# ACC_Register_Electronic_Scheme_2021-10-0.net
KiCad netlist of a schematic drawn in Altium Designer
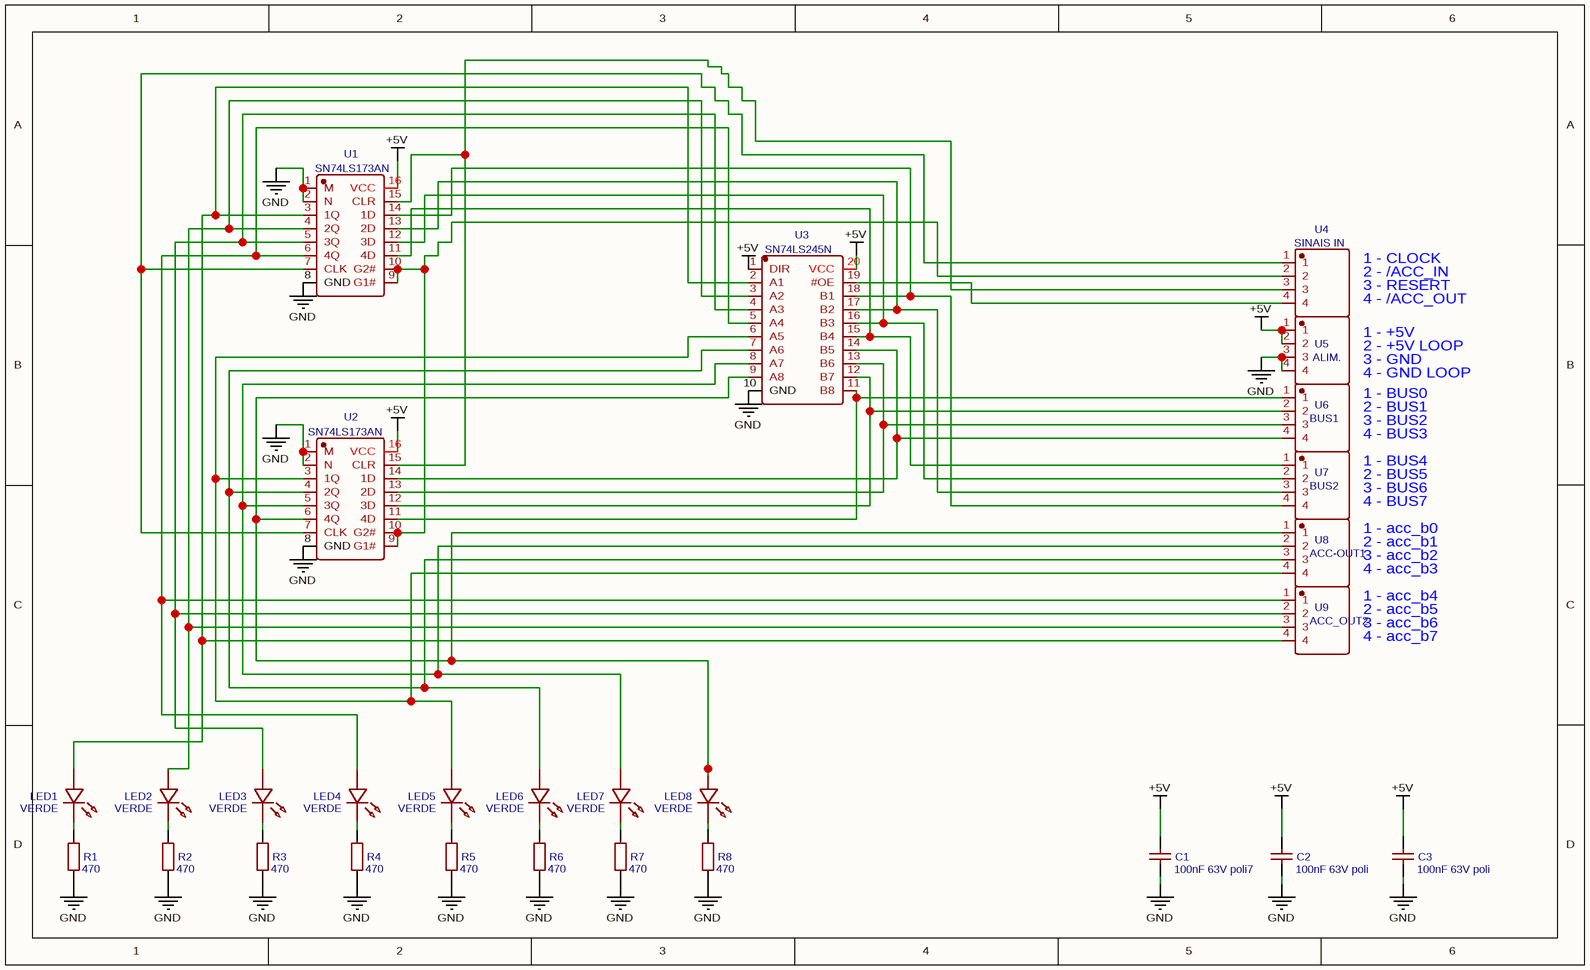
[diagram p0: ACC Register Electronic Scheme_2021-10-02.schdoc]

(export (version "E")
  (design (tool "Eeschema 10.0.6"))
  (components
    (comp (ref "C1")
      (value "100nF 63V poli7")
      (fields
        (field (name "BOM_SUPPLIER PART") "C444741")
        (field (name "BOM_MANUFACTURER PART") "SR305C105KAR")
        (field (name "CONTRIBUTOR") "LCSC")
      )
      (libsource (lib "altium-import") (part "root_3_100nF 63V poli7_"))
    )
    (comp (ref "C2")
      (value "100nF 63V poli")
      (fields
        (field (name "BOM_SUPPLIER PART") "C444741")
        (field (name "BOM_MANUFACTURER PART") "SR305C105KAR")
        (field (name "CONTRIBUTOR") "LCSC")
      )
      (libsource (lib "altium-import") (part "root_3_100nF 63V poli_"))
    )
    (comp (ref "C3")
      (value "100nF 63V poli")
      (fields
        (field (name "BOM_SUPPLIER PART") "C444741")
        (field (name "BOM_MANUFACTURER PART") "SR305C105KAR")
        (field (name "CONTRIBUTOR") "LCSC")
      )
      (libsource (lib "altium-import") (part "root_3_100nF 63V poli_"))
    )
    (comp (ref "LED1")
      (value "VERDE")
      (fields
        (field (name "BOM_SUPPLIER PART") "C605465")
        (field (name "BOM_MANUFACTURER PART") "264-7GD")
        (field (name "CONTRIBUTOR") "LCSC")
      )
      (libsource (lib "altium-import") (part "root_1_VERDE_"))
    )
    (comp (ref "LED2")
      (value "VERDE")
      (fields
        (field (name "BOM_SUPPLIER PART") "C605465")
        (field (name "BOM_MANUFACTURER PART") "264-7GD")
        (field (name "CONTRIBUTOR") "LCSC")
      )
      (libsource (lib "altium-import") (part "root_1_VERDE_"))
    )
    (comp (ref "LED3")
      (value "VERDE")
      (fields
        (field (name "BOM_SUPPLIER PART") "C605465")
        (field (name "BOM_MANUFACTURER PART") "264-7GD")
        (field (name "CONTRIBUTOR") "LCSC")
      )
      (libsource (lib "altium-import") (part "root_1_VERDE_"))
    )
    (comp (ref "LED4")
      (value "VERDE")
      (fields
        (field (name "BOM_SUPPLIER PART") "C605465")
        (field (name "BOM_MANUFACTURER PART") "264-7GD")
        (field (name "CONTRIBUTOR") "LCSC")
      )
      (libsource (lib "altium-import") (part "root_1_VERDE_"))
    )
    (comp (ref "LED5")
      (value "VERDE")
      (fields
        (field (name "BOM_SUPPLIER PART") "C605465")
        (field (name "BOM_MANUFACTURER PART") "264-7GD")
        (field (name "CONTRIBUTOR") "LCSC")
      )
      (libsource (lib "altium-import") (part "root_1_VERDE_"))
    )
    (comp (ref "LED6")
      (value "VERDE")
      (fields
        (field (name "BOM_SUPPLIER PART") "C605465")
        (field (name "BOM_MANUFACTURER PART") "264-7GD")
        (field (name "CONTRIBUTOR") "LCSC")
      )
      (libsource (lib "altium-import") (part "root_1_VERDE_"))
    )
    (comp (ref "LED7")
      (value "VERDE")
      (fields
        (field (name "BOM_SUPPLIER PART") "C605465")
        (field (name "BOM_MANUFACTURER PART") "264-7GD")
        (field (name "CONTRIBUTOR") "LCSC")
      )
      (libsource (lib "altium-import") (part "root_1_VERDE_"))
    )
    (comp (ref "LED8")
      (value "VERDE")
      (fields
        (field (name "BOM_SUPPLIER PART") "C605465")
        (field (name "BOM_MANUFACTURER PART") "264-7GD")
        (field (name "CONTRIBUTOR") "LCSC")
      )
      (libsource (lib "altium-import") (part "root_1_VERDE_"))
    )
    (comp (ref "R1")
      (value "470")
      (fields
        (field (name "BOM_MANUFACTURER PART") "CFR02SJ0823A10")
        (field (name "BOM_SUPPLIER PART") "C69876")
      )
      (libsource (lib "altium-import") (part "root_3_470_"))
    )
    (comp (ref "R2")
      (value "470")
      (fields
        (field (name "BOM_MANUFACTURER PART") "CFR02SJ0823A10")
        (field (name "BOM_SUPPLIER PART") "C69876")
      )
      (libsource (lib "altium-import") (part "root_3_470_"))
    )
    (comp (ref "R3")
      (value "470")
      (fields
        (field (name "BOM_MANUFACTURER PART") "CFR02SJ0823A10")
        (field (name "BOM_SUPPLIER PART") "C69876")
      )
      (libsource (lib "altium-import") (part "root_3_470_"))
    )
    (comp (ref "R4")
      (value "470")
      (fields
        (field (name "BOM_MANUFACTURER PART") "CFR02SJ0823A10")
        (field (name "BOM_SUPPLIER PART") "C69876")
      )
      (libsource (lib "altium-import") (part "root_3_470_"))
    )
    (comp (ref "R5")
      (value "470")
      (fields
        (field (name "BOM_MANUFACTURER PART") "CFR02SJ0823A10")
        (field (name "BOM_SUPPLIER PART") "C69876")
      )
      (libsource (lib "altium-import") (part "root_3_470_"))
    )
    (comp (ref "R6")
      (value "470")
      (fields
        (field (name "BOM_MANUFACTURER PART") "CFR02SJ0823A10")
        (field (name "BOM_SUPPLIER PART") "C69876")
      )
      (libsource (lib "altium-import") (part "root_3_470_"))
    )
    (comp (ref "R7")
      (value "470")
      (fields
        (field (name "BOM_MANUFACTURER PART") "CFR02SJ0823A10")
        (field (name "BOM_SUPPLIER PART") "C69876")
      )
      (libsource (lib "altium-import") (part "root_3_470_"))
    )
    (comp (ref "R8")
      (value "470")
      (fields
        (field (name "BOM_MANUFACTURER PART") "CFR02SJ0823A10")
        (field (name "BOM_SUPPLIER PART") "C69876")
      )
      (libsource (lib "altium-import") (part "root_3_470_"))
    )
    (comp (ref "U1")
      (value "SN74LS173AN")
      (fields (field (name "BOM_SUPPLIER PART") "C1550125") (field (name "CONTRIBUTOR") "LCSC"))
      (libsource (lib "altium-import") (part "root_0_SN74LS173AN_"))
    )
    (comp (ref "U2")
      (value "SN74LS173AN")
      (fields (field (name "BOM_SUPPLIER PART") "C1550125") (field (name "CONTRIBUTOR") "LCSC"))
      (libsource (lib "altium-import") (part "root_0_SN74LS173AN_"))
    )
    (comp (ref "U3")
      (value "SN74LS245N")
      (fields (field (name "BOM_SUPPLIER PART") "C352966") (field (name "CONTRIBUTOR") "LCSC"))
      (libsource (lib "altium-import") (part "root_0_SN74LS245N_"))
    )
    (comp (ref "U4")
      (value "SINAIS IN")
      (fields
        (field (name "BOM_SUPPLIER PART") "C210162")
        (field (name "BOM_MANUFACTURER PART") "171825-4")
        (field (name "CONTRIBUTOR") "LCSC")
      )
      (libsource (lib "altium-import") (part "root_0_SINAIS IN_"))
    )
    (comp (ref "U5")
      (value "ALIM.")
      (fields
        (field (name "BOM_SUPPLIER PART") "C210162")
        (field (name "BOM_MANUFACTURER PART") "171825-4")
        (field (name "CONTRIBUTOR") "LCSC")
      )
      (libsource (lib "altium-import") (part "root_0_ALIM._"))
    )
    (comp (ref "U6")
      (value "BUS1")
      (fields
        (field (name "BOM_SUPPLIER PART") "C210162")
        (field (name "BOM_MANUFACTURER PART") "171825-4")
        (field (name "CONTRIBUTOR") "LCSC")
      )
      (libsource (lib "altium-import") (part "root_0_BUS1_"))
    )
    (comp (ref "U7")
      (value "BUS2")
      (fields
        (field (name "BOM_SUPPLIER PART") "C210162")
        (field (name "BOM_MANUFACTURER PART") "171825-4")
        (field (name "CONTRIBUTOR") "LCSC")
      )
      (libsource (lib "altium-import") (part "root_0_BUS2_"))
    )
    (comp (ref "U8")
      (value "ACC-OUT1")
      (fields
        (field (name "BOM_SUPPLIER PART") "C210162")
        (field (name "BOM_MANUFACTURER PART") "171825-4")
        (field (name "CONTRIBUTOR") "LCSC")
      )
      (libsource (lib "altium-import") (part "root_0_ACC-OUT1_"))
    )
    (comp (ref "U9")
      (value "ACC_OUT2")
      (fields
        (field (name "BOM_SUPPLIER PART") "C210162")
        (field (name "BOM_MANUFACTURER PART") "171825-4")
        (field (name "CONTRIBUTOR") "LCSC")
      )
      (libsource (lib "altium-import") (part "root_0_ACC_OUT2_"))
    )
  )
  (nets
    (net (code "1") (name "+5V") (class "Default")
      (node (ref "C1") (pin "1") (pinfunction "1_1") (pintype "passive"))
      (node (ref "C2") (pin "1") (pinfunction "1_1") (pintype "passive"))
      (node (ref "C3") (pin "1") (pinfunction "1_1") (pintype "passive"))
      (node (ref "U1") (pin "16") (pinfunction "VCC_16") (pintype "passive"))
      (node (ref "U2") (pin "16") (pinfunction "VCC_16") (pintype "passive"))
      (node (ref "U3") (pin "1") (pinfunction "DIR_1") (pintype "passive"))
      (node (ref "U3") (pin "20") (pinfunction "VCC_20") (pintype "passive"))
      (node (ref "U5") (pin "1") (pinfunction "1_1") (pintype "passive"))
      (node (ref "U5") (pin "2") (pinfunction "2_2") (pintype "passive"))
    )
    (net (code "2") (name "GND") (class "Default")
      (node (ref "C1") (pin "2") (pinfunction "2_2") (pintype "passive"))
      (node (ref "C2") (pin "2") (pinfunction "2_2") (pintype "passive"))
      (node (ref "C3") (pin "2") (pinfunction "2_2") (pintype "passive"))
      (node (ref "R1") (pin "2") (pinfunction "2_2") (pintype "passive"))
      (node (ref "R2") (pin "2") (pinfunction "2_2") (pintype "passive"))
      (node (ref "R3") (pin "2") (pinfunction "2_2") (pintype "passive"))
      (node (ref "R4") (pin "2") (pinfunction "2_2") (pintype "passive"))
      (node (ref "R5") (pin "2") (pinfunction "2_2") (pintype "passive"))
      (node (ref "R6") (pin "2") (pinfunction "2_2") (pintype "passive"))
      (node (ref "R7") (pin "2") (pinfunction "2_2") (pintype "passive"))
      (node (ref "R8") (pin "2") (pinfunction "2_2") (pintype "passive"))
      (node (ref "U1") (pin "1") (pinfunction "M_1") (pintype "passive"))
      (node (ref "U1") (pin "2") (pinfunction "N_2") (pintype "passive"))
      (node (ref "U1") (pin "8") (pinfunction "GND_8") (pintype "passive"))
      (node (ref "U2") (pin "1") (pinfunction "M_1") (pintype "passive"))
      (node (ref "U2") (pin "2") (pinfunction "N_2") (pintype "passive"))
      (node (ref "U2") (pin "8") (pinfunction "GND_8") (pintype "passive"))
      (node (ref "U3") (pin "10") (pinfunction "GND_10") (pintype "passive"))
      (node (ref "U5") (pin "3") (pinfunction "3_3") (pintype "passive"))
      (node (ref "U5") (pin "4") (pinfunction "4_4") (pintype "passive"))
    )
    (net (code "3") (name "Net-(LED1-+)") (class "Default")
      (node (ref "LED1") (pin "2") (pinfunction "+_2") (pintype "passive"))
      (node (ref "U1") (pin "3") (pinfunction "1Q_3") (pintype "passive"))
      (node (ref "U3") (pin "2") (pinfunction "A1_2") (pintype "passive"))
      (node (ref "U9") (pin "4") (pinfunction "4_4") (pintype "passive"))
    )
    (net (code "4") (name "Net-(LED1--)") (class "Default")
      (node (ref "LED1") (pin "1") (pinfunction "-_1") (pintype "passive"))
      (node (ref "R1") (pin "1") (pinfunction "1_1") (pintype "passive"))
    )
    (net (code "5") (name "Net-(LED2-+)") (class "Default")
      (node (ref "LED2") (pin "2") (pinfunction "+_2") (pintype "passive"))
      (node (ref "U1") (pin "4") (pinfunction "2Q_4") (pintype "passive"))
      (node (ref "U3") (pin "3") (pinfunction "A2_3") (pintype "passive"))
      (node (ref "U9") (pin "3") (pinfunction "3_3") (pintype "passive"))
    )
    (net (code "6") (name "Net-(LED2--)") (class "Default")
      (node (ref "LED2") (pin "1") (pinfunction "-_1") (pintype "passive"))
      (node (ref "R2") (pin "1") (pinfunction "1_1") (pintype "passive"))
    )
    (net (code "7") (name "Net-(LED3-+)") (class "Default")
      (node (ref "LED3") (pin "2") (pinfunction "+_2") (pintype "passive"))
      (node (ref "U1") (pin "5") (pinfunction "3Q_5") (pintype "passive"))
      (node (ref "U3") (pin "4") (pinfunction "A3_4") (pintype "passive"))
      (node (ref "U9") (pin "2") (pinfunction "2_2") (pintype "passive"))
    )
    (net (code "8") (name "Net-(LED3--)") (class "Default")
      (node (ref "LED3") (pin "1") (pinfunction "-_1") (pintype "passive"))
      (node (ref "R3") (pin "1") (pinfunction "1_1") (pintype "passive"))
    )
    (net (code "9") (name "Net-(LED4-+)") (class "Default")
      (node (ref "LED4") (pin "2") (pinfunction "+_2") (pintype "passive"))
      (node (ref "U1") (pin "6") (pinfunction "4Q_6") (pintype "passive"))
      (node (ref "U3") (pin "5") (pinfunction "A4_5") (pintype "passive"))
      (node (ref "U9") (pin "1") (pinfunction "1_1") (pintype "passive"))
    )
    (net (code "10") (name "Net-(LED4--)") (class "Default")
      (node (ref "LED4") (pin "1") (pinfunction "-_1") (pintype "passive"))
      (node (ref "R4") (pin "1") (pinfunction "1_1") (pintype "passive"))
    )
    (net (code "11") (name "Net-(LED5-+)") (class "Default")
      (node (ref "LED5") (pin "2") (pinfunction "+_2") (pintype "passive"))
      (node (ref "U2") (pin "3") (pinfunction "1Q_3") (pintype "passive"))
      (node (ref "U3") (pin "6") (pinfunction "A5_6") (pintype "passive"))
      (node (ref "U8") (pin "4") (pinfunction "4_4") (pintype "passive"))
    )
    (net (code "12") (name "Net-(LED5--)") (class "Default")
      (node (ref "LED5") (pin "1") (pinfunction "-_1") (pintype "passive"))
      (node (ref "R5") (pin "1") (pinfunction "1_1") (pintype "passive"))
    )
    (net (code "13") (name "Net-(LED6-+)") (class "Default")
      (node (ref "LED6") (pin "2") (pinfunction "+_2") (pintype "passive"))
      (node (ref "U2") (pin "4") (pinfunction "2Q_4") (pintype "passive"))
      (node (ref "U3") (pin "7") (pinfunction "A6_7") (pintype "passive"))
      (node (ref "U8") (pin "3") (pinfunction "3_3") (pintype "passive"))
    )
    (net (code "14") (name "Net-(LED6--)") (class "Default")
      (node (ref "LED6") (pin "1") (pinfunction "-_1") (pintype "passive"))
      (node (ref "R6") (pin "1") (pinfunction "1_1") (pintype "passive"))
    )
    (net (code "15") (name "Net-(LED7-+)") (class "Default")
      (node (ref "LED7") (pin "2") (pinfunction "+_2") (pintype "passive"))
      (node (ref "U2") (pin "5") (pinfunction "3Q_5") (pintype "passive"))
      (node (ref "U3") (pin "8") (pinfunction "A7_8") (pintype "passive"))
      (node (ref "U8") (pin "2") (pinfunction "2_2") (pintype "passive"))
    )
    (net (code "16") (name "Net-(LED7--)") (class "Default")
      (node (ref "LED7") (pin "1") (pinfunction "-_1") (pintype "passive"))
      (node (ref "R7") (pin "1") (pinfunction "1_1") (pintype "passive"))
    )
    (net (code "17") (name "Net-(LED8-+)") (class "Default")
      (node (ref "LED8") (pin "2") (pinfunction "+_2") (pintype "passive"))
      (node (ref "U2") (pin "6") (pinfunction "4Q_6") (pintype "passive"))
      (node (ref "U3") (pin "9") (pinfunction "A8_9") (pintype "passive"))
      (node (ref "U8") (pin "1") (pinfunction "1_1") (pintype "passive"))
    )
    (net (code "18") (name "Net-(LED8--)") (class "Default")
      (node (ref "LED8") (pin "1") (pinfunction "-_1") (pintype "passive"))
      (node (ref "R8") (pin "1") (pinfunction "1_1") (pintype "passive"))
    )
    (net (code "19") (name "Net-(U1-1D)") (class "Default")
      (node (ref "U1") (pin "14") (pinfunction "1D_14") (pintype "passive"))
      (node (ref "U3") (pin "18") (pinfunction "B1_18") (pintype "passive"))
      (node (ref "U7") (pin "4") (pinfunction "4_4") (pintype "passive"))
    )
    (net (code "20") (name "Net-(U1-2D)") (class "Default")
      (node (ref "U1") (pin "13") (pinfunction "2D_13") (pintype "passive"))
      (node (ref "U3") (pin "17") (pinfunction "B2_17") (pintype "passive"))
      (node (ref "U7") (pin "3") (pinfunction "3_3") (pintype "passive"))
    )
    (net (code "21") (name "Net-(U1-3D)") (class "Default")
      (node (ref "U1") (pin "12") (pinfunction "3D_12") (pintype "passive"))
      (node (ref "U3") (pin "16") (pinfunction "B3_16") (pintype "passive"))
      (node (ref "U7") (pin "2") (pinfunction "2_2") (pintype "passive"))
    )
    (net (code "22") (name "Net-(U1-4D)") (class "Default")
      (node (ref "U1") (pin "11") (pinfunction "4D_11") (pintype "passive"))
      (node (ref "U3") (pin "15") (pinfunction "B4_15") (pintype "passive"))
      (node (ref "U7") (pin "1") (pinfunction "1_1") (pintype "passive"))
    )
    (net (code "23") (name "Net-(U1-CLK)") (class "Default")
      (node (ref "U1") (pin "7") (pinfunction "CLK_7") (pintype "passive"))
      (node (ref "U2") (pin "7") (pinfunction "CLK_7") (pintype "passive"))
      (node (ref "U4") (pin "1") (pinfunction "1_1") (pintype "passive"))
    )
    (net (code "24") (name "Net-(U1-CLR)") (class "Default")
      (node (ref "U1") (pin "15") (pinfunction "CLR_15") (pintype "passive"))
      (node (ref "U2") (pin "15") (pinfunction "CLR_15") (pintype "passive"))
      (node (ref "U4") (pin "3") (pinfunction "3_3") (pintype "passive"))
    )
    (net (code "25") (name "Net-(U1-G1#)") (class "Default")
      (node (ref "U1") (pin "10") (pinfunction "G2#_10") (pintype "passive"))
      (node (ref "U1") (pin "9") (pinfunction "G1#_9") (pintype "passive"))
      (node (ref "U2") (pin "10") (pinfunction "G2#_10") (pintype "passive"))
      (node (ref "U2") (pin "9") (pinfunction "G1#_9") (pintype "passive"))
      (node (ref "U4") (pin "2") (pinfunction "2_2") (pintype "passive"))
    )
    (net (code "26") (name "Net-(U2-1D)") (class "Default")
      (node (ref "U2") (pin "14") (pinfunction "1D_14") (pintype "passive"))
      (node (ref "U3") (pin "14") (pinfunction "B5_14") (pintype "passive"))
      (node (ref "U6") (pin "4") (pinfunction "4_4") (pintype "passive"))
    )
    (net (code "27") (name "Net-(U2-2D)") (class "Default")
      (node (ref "U2") (pin "13") (pinfunction "2D_13") (pintype "passive"))
      (node (ref "U3") (pin "13") (pinfunction "B6_13") (pintype "passive"))
      (node (ref "U6") (pin "3") (pinfunction "3_3") (pintype "passive"))
    )
    (net (code "28") (name "Net-(U2-3D)") (class "Default")
      (node (ref "U2") (pin "12") (pinfunction "3D_12") (pintype "passive"))
      (node (ref "U3") (pin "12") (pinfunction "B7_12") (pintype "passive"))
      (node (ref "U6") (pin "2") (pinfunction "2_2") (pintype "passive"))
    )
    (net (code "29") (name "Net-(U2-4D)") (class "Default")
      (node (ref "U2") (pin "11") (pinfunction "4D_11") (pintype "passive"))
      (node (ref "U3") (pin "11") (pinfunction "B8_11") (pintype "passive"))
      (node (ref "U6") (pin "1") (pinfunction "1_1") (pintype "passive"))
    )
    (net (code "30") (name "Net-(U3-#OE)") (class "Default")
      (node (ref "U3") (pin "19") (pinfunction "#OE_19") (pintype "passive"))
      (node (ref "U4") (pin "4") (pinfunction "4_4") (pintype "passive"))
    )
  )
)
